# Switcher.net
KiCad netlist of a schematic drawn in Altium Designer
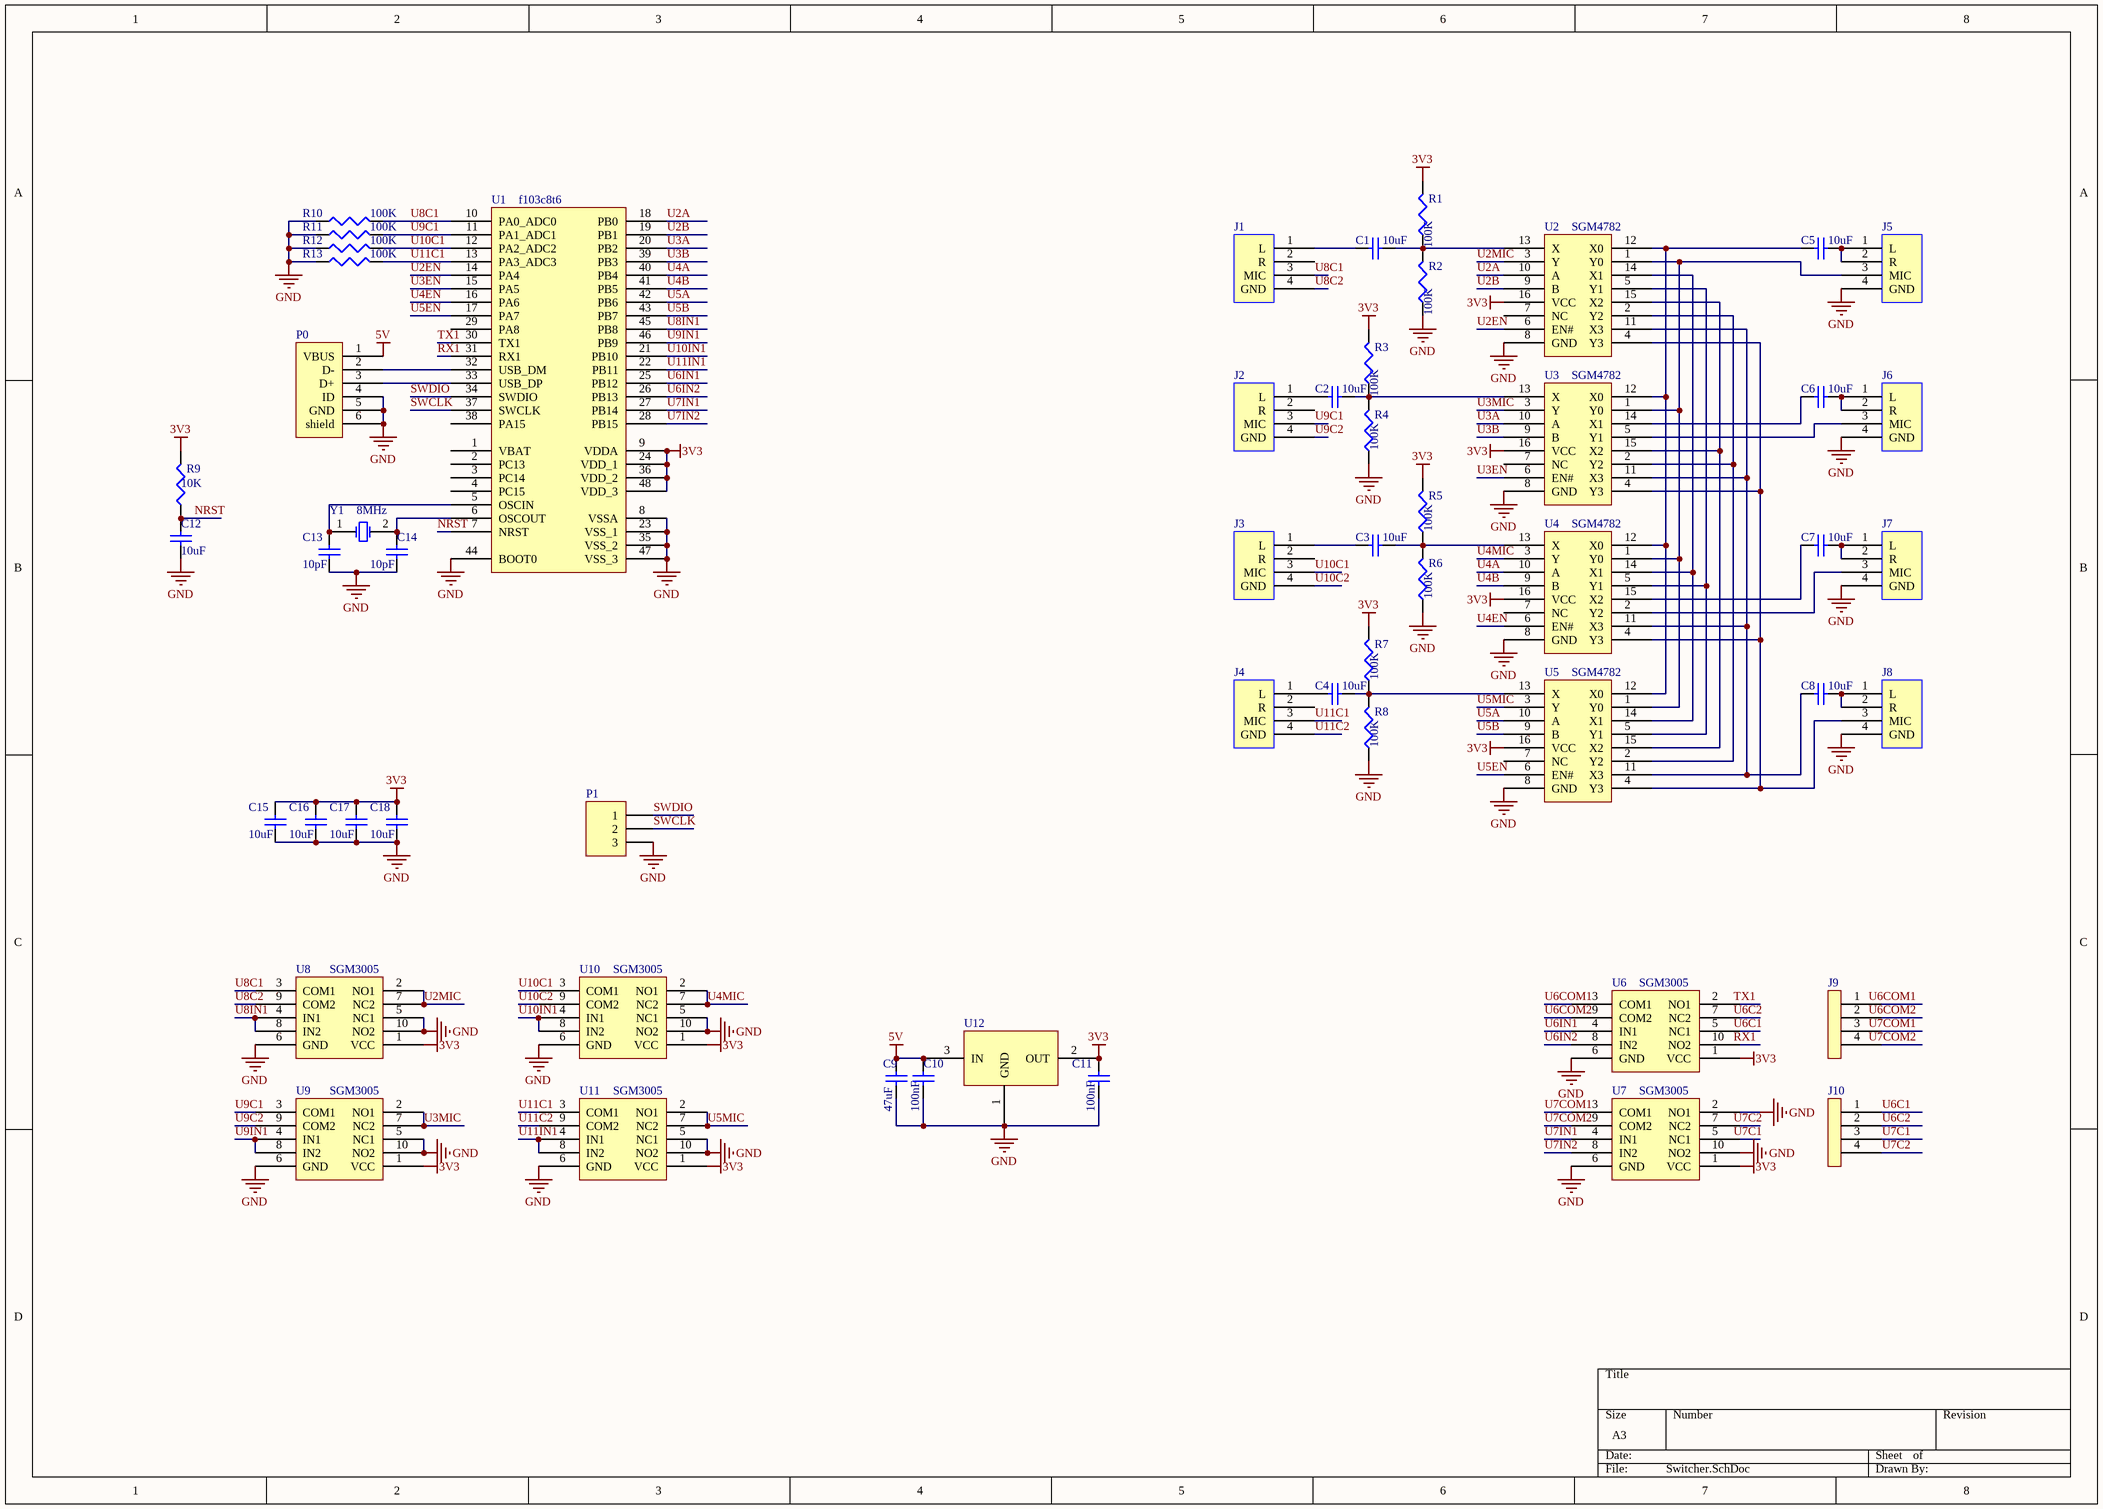
[diagram p0: Switcher.SchDoc]

(export (version "E")
  (design (tool "Eeschema 10.0.6"))
  (components
    (comp (ref "C1")
      (value "10uF")
      (footprint "1608(0603C)")
      (description "Capacitor")
      (fields (field (name "PUBLISHER") "Altium Limited"))
      (libsource (lib "Miscellaneous Devices") (part "Cap"))
    )
    (comp (ref "C2")
      (value "10uF")
      (footprint "1608(0603C)")
      (description "Capacitor")
      (fields (field (name "PUBLISHER") "Altium Limited"))
      (libsource (lib "Miscellaneous Devices") (part "Cap"))
    )
    (comp (ref "C3")
      (value "10uF")
      (footprint "1608(0603C)")
      (description "Capacitor")
      (fields (field (name "PUBLISHER") "Altium Limited"))
      (libsource (lib "Miscellaneous Devices") (part "Cap"))
    )
    (comp (ref "C4")
      (value "10uF")
      (footprint "1608(0603C)")
      (description "Capacitor")
      (fields (field (name "PUBLISHER") "Altium Limited"))
      (libsource (lib "Miscellaneous Devices") (part "Cap"))
    )
    (comp (ref "C5")
      (value "10uF")
      (footprint "1608(0603C)")
      (description "Capacitor")
      (fields (field (name "PUBLISHER") "Altium Limited"))
      (libsource (lib "Miscellaneous Devices") (part "Cap"))
    )
    (comp (ref "C6")
      (value "10uF")
      (footprint "1608(0603C)")
      (description "Capacitor")
      (fields (field (name "PUBLISHER") "Altium Limited"))
      (libsource (lib "Miscellaneous Devices") (part "Cap"))
    )
    (comp (ref "C7")
      (value "10uF")
      (footprint "1608(0603C)")
      (description "Capacitor")
      (fields (field (name "PUBLISHER") "Altium Limited"))
      (libsource (lib "Miscellaneous Devices") (part "Cap"))
    )
    (comp (ref "C8")
      (value "10uF")
      (footprint "1608(0603C)")
      (description "Capacitor")
      (fields (field (name "PUBLISHER") "Altium Limited"))
      (libsource (lib "Miscellaneous Devices") (part "Cap"))
    )
    (comp (ref "C9")
      (value "47uF")
      (footprint "1608(0603C)")
      (description "Capacitor")
      (fields (field (name "PUBLISHER") "Altium Limited"))
      (libsource (lib "Miscellaneous Devices") (part "Cap"))
    )
    (comp (ref "C10")
      (value "100nF")
      (footprint "1608(0603C)")
      (description "Capacitor")
      (fields (field (name "PUBLISHER") "Altium Limited"))
      (libsource (lib "Miscellaneous Devices") (part "Cap"))
    )
    (comp (ref "C11")
      (value "100nF")
      (footprint "1608(0603C)")
      (description "Capacitor")
      (fields (field (name "PUBLISHER") "Altium Limited"))
      (libsource (lib "Miscellaneous Devices") (part "Cap"))
    )
    (comp (ref "C12")
      (value "10uF")
      (footprint "1608(0603C)")
      (description "Capacitor")
      (fields (field (name "PUBLISHER") "Altium Limited"))
      (libsource (lib "Miscellaneous Devices") (part "Cap"))
    )
    (comp (ref "C13")
      (value "10pF")
      (footprint "1608(0603C)")
      (description "Capacitor")
      (fields (field (name "PUBLISHER") "Altium Limited"))
      (libsource (lib "Miscellaneous Devices") (part "Cap"))
    )
    (comp (ref "C14")
      (value "10pF")
      (footprint "1608(0603C)")
      (description "Capacitor")
      (fields (field (name "PUBLISHER") "Altium Limited"))
      (libsource (lib "Miscellaneous Devices") (part "Cap"))
    )
    (comp (ref "C15")
      (value "10uF")
      (footprint "1608(0603C)")
      (description "Capacitor")
      (fields (field (name "PUBLISHER") "Altium Limited"))
      (libsource (lib "Miscellaneous Devices") (part "Cap"))
    )
    (comp (ref "C16")
      (value "10uF")
      (footprint "1608(0603C)")
      (description "Capacitor")
      (fields (field (name "PUBLISHER") "Altium Limited"))
      (libsource (lib "Miscellaneous Devices") (part "Cap"))
    )
    (comp (ref "C17")
      (value "10uF")
      (footprint "1608(0603C)")
      (description "Capacitor")
      (fields (field (name "PUBLISHER") "Altium Limited"))
      (libsource (lib "Miscellaneous Devices") (part "Cap"))
    )
    (comp (ref "C18")
      (value "10uF")
      (footprint "1608(0603C)")
      (description "Capacitor")
      (fields (field (name "PUBLISHER") "Altium Limited"))
      (libsource (lib "Miscellaneous Devices") (part "Cap"))
    )
    (comp (ref "J1") (value "~") (footprint "PJ-322") (libsource (lib "Switcher") (part "seg-4")))
    (comp (ref "J2") (value "~") (footprint "PJ-322") (libsource (lib "Switcher") (part "seg-4")))
    (comp (ref "J3") (value "~") (footprint "PJ-322") (libsource (lib "Switcher") (part "seg-4")))
    (comp (ref "J4") (value "~") (footprint "PJ-322") (libsource (lib "Switcher") (part "seg-4")))
    (comp (ref "J5")
      (value "~")
      (footprint "PJ-322")
      (description "OMTP")
      (libsource (lib "") (part "seg-4_1"))
    )
    (comp (ref "J6") (value "~") (footprint "PJ-322") (libsource (lib "") (part "seg-4_1")))
    (comp (ref "J7") (value "~") (footprint "PJ-322") (libsource (lib "") (part "seg-4_1")))
    (comp (ref "J8") (value "~") (footprint "PJ-322") (libsource (lib "") (part "seg-4_1")))
    (comp (ref "J9") (value "~") (footprint "PJ-322") (libsource (lib "Switcher") (part "CON4")))
    (comp (ref "J10") (value "~") (footprint "PJ-322") (libsource (lib "Switcher") (part "CON4")))
    (comp (ref "P0") (value "~") (footprint "USB_MICRO") (libsource (lib "Switcher") (part "micro_usb")))
    (comp (ref "P1")
      (value "~")
      (footprint "SIP3")
      (description "Header, 3-Pin")
      (fields (field (name "PUBLISHER") "Altium Limited"))
      (libsource (lib "Miscellaneous Connectors") (part "Header 3"))
    )
    (comp (ref "R1")
      (value "100K")
      (footprint "1608(0603R)")
      (description "Resistor")
      (fields (field (name "PUBLISHER") "Altium Limited"))
      (libsource (lib "Miscellaneous Devices") (part "Res3"))
    )
    (comp (ref "R2")
      (value "100K")
      (footprint "1608(0603R)")
      (description "Resistor")
      (fields (field (name "PUBLISHER") "Altium Limited"))
      (libsource (lib "Miscellaneous Devices") (part "Res3"))
    )
    (comp (ref "R3")
      (value "100K")
      (footprint "1608(0603R)")
      (description "Resistor")
      (fields (field (name "PUBLISHER") "Altium Limited"))
      (libsource (lib "Miscellaneous Devices") (part "Res3"))
    )
    (comp (ref "R4")
      (value "100K")
      (footprint "1608(0603R)")
      (description "Resistor")
      (fields (field (name "PUBLISHER") "Altium Limited"))
      (libsource (lib "Miscellaneous Devices") (part "Res3"))
    )
    (comp (ref "R5")
      (value "100K")
      (footprint "1608(0603R)")
      (description "Resistor")
      (fields (field (name "PUBLISHER") "Altium Limited"))
      (libsource (lib "Miscellaneous Devices") (part "Res3"))
    )
    (comp (ref "R6")
      (value "100K")
      (footprint "1608(0603R)")
      (description "Resistor")
      (fields (field (name "PUBLISHER") "Altium Limited"))
      (libsource (lib "Miscellaneous Devices") (part "Res3"))
    )
    (comp (ref "R7")
      (value "100K")
      (footprint "1608(0603R)")
      (description "Resistor")
      (fields (field (name "PUBLISHER") "Altium Limited"))
      (libsource (lib "Miscellaneous Devices") (part "Res3"))
    )
    (comp (ref "R8")
      (value "100K")
      (footprint "1608(0603R)")
      (description "Resistor")
      (fields (field (name "PUBLISHER") "Altium Limited"))
      (libsource (lib "Miscellaneous Devices") (part "Res3"))
    )
    (comp (ref "R9")
      (value "10K")
      (footprint "1608(0603R)")
      (description "Resistor")
      (fields (field (name "PUBLISHER") "Altium Limited"))
      (libsource (lib "Miscellaneous Devices") (part "Res3"))
    )
    (comp (ref "R10")
      (value "100K")
      (footprint "1608(0603R)")
      (description "Resistor")
      (fields (field (name "PUBLISHER") "Altium Limited"))
      (libsource (lib "Miscellaneous Devices") (part "Res3"))
    )
    (comp (ref "R11")
      (value "100K")
      (footprint "1608(0603R)")
      (description "Resistor")
      (fields (field (name "PUBLISHER") "Altium Limited"))
      (libsource (lib "Miscellaneous Devices") (part "Res3"))
    )
    (comp (ref "R12")
      (value "100K")
      (footprint "1608(0603R)")
      (description "Resistor")
      (fields (field (name "PUBLISHER") "Altium Limited"))
      (libsource (lib "Miscellaneous Devices") (part "Res3"))
    )
    (comp (ref "R13")
      (value "100K")
      (footprint "1608(0603R)")
      (description "Resistor")
      (fields (field (name "PUBLISHER") "Altium Limited"))
      (libsource (lib "Miscellaneous Devices") (part "Res3"))
    )
    (comp (ref "U1") (value "f103c8t6") (footprint "LQFP48") (libsource (lib "Switcher") (part "f103c8t6")))
    (comp (ref "U2") (value "SGM4782") (footprint "TSSOP-16") (libsource (lib "Switcher") (part "SGM4782")))
    (comp (ref "U3") (value "SGM4782") (footprint "TSSOP-16") (libsource (lib "Switcher") (part "SGM4782")))
    (comp (ref "U4") (value "SGM4782") (footprint "TSSOP-16") (libsource (lib "Switcher") (part "SGM4782")))
    (comp (ref "U5") (value "SGM4782") (footprint "TSSOP-16") (libsource (lib "Switcher") (part "SGM4782")))
    (comp (ref "U6") (value "SGM3005") (footprint "MSOP-10") (libsource (lib "Switcher") (part "SGM3005")))
    (comp (ref "U7") (value "SGM3005") (footprint "MSOP-10") (libsource (lib "Switcher") (part "SGM3005")))
    (comp (ref "U8") (value "SGM3005") (footprint "MSOP-10") (libsource (lib "Switcher") (part "SGM3005")))
    (comp (ref "U9") (value "SGM3005") (footprint "MSOP-10") (libsource (lib "Switcher") (part "SGM3005")))
    (comp (ref "U10") (value "SGM3005") (footprint "MSOP-10") (libsource (lib "Switcher") (part "SGM3005")))
    (comp (ref "U11") (value "SGM3005") (footprint "MSOP-10") (libsource (lib "Switcher") (part "SGM3005")))
    (comp (ref "U12") (value "~") (footprint "SOT-223") (libsource (lib "Switcher") (part "ASM1117-3.3")))
    (comp (ref "Y1")
      (value "8MHz")
      (footprint "XTAL1")
      (description "Crystal Oscillator")
      (fields (field (name "PUBLISHER") "Altium Limited"))
      (libsource (lib "Miscellaneous Devices") (part "XTAL"))
    )
  )
  (nets
    (net (code "1") (name "/NRST") (class "Default")
      (node (ref "C12") (pin "2") (pinfunction "2_2") (pintype "passive"))
      (node (ref "R9") (pin "1") (pinfunction "1_1") (pintype "passive"))
      (node (ref "U1") (pin "7") (pinfunction "NRST_7") (pintype "passive"))
    )
    (net (code "2") (name "/RX1") (class "Default")
      (node (ref "U1") (pin "31") (pinfunction "RX1_31") (pintype "passive"))
    )
    (net (code "3") (name "/SWCLK") (class "Default")
      (node (ref "P1") (pin "2") (pinfunction "2_2") (pintype "passive"))
      (node (ref "U1") (pin "37") (pinfunction "SWCLK_37") (pintype "passive"))
    )
    (net (code "4") (name "/SWDIO") (class "Default")
      (node (ref "P1") (pin "1") (pinfunction "1_1") (pintype "passive"))
      (node (ref "U1") (pin "34") (pinfunction "SWDIO_34") (pintype "passive"))
    )
    (net (code "5") (name "/TX1") (class "Default")
      (node (ref "U1") (pin "30") (pinfunction "TX1_30") (pintype "passive"))
    )
    (net (code "6") (name "/U2A") (class "Default")
      (node (ref "U1") (pin "18") (pinfunction "PB0_18") (pintype "passive"))
      (node (ref "U2") (pin "10") (pinfunction "A_10") (pintype "passive"))
    )
    (net (code "7") (name "/U2B") (class "Default")
      (node (ref "U1") (pin "19") (pinfunction "PB1_19") (pintype "passive"))
      (node (ref "U2") (pin "9") (pinfunction "B_9") (pintype "passive"))
    )
    (net (code "8") (name "/U2EN") (class "Default")
      (node (ref "U1") (pin "14") (pinfunction "PA4_14") (pintype "passive"))
      (node (ref "U2") (pin "6") (pinfunction "EN#_6") (pintype "passive"))
    )
    (net (code "9") (name "/U2MIC") (class "Default")
      (node (ref "U2") (pin "3") (pinfunction "Y_3") (pintype "passive"))
      (node (ref "U8") (pin "2") (pinfunction "NO1_2") (pintype "passive"))
      (node (ref "U8") (pin "7") (pinfunction "NC2_7") (pintype "passive"))
    )
    (net (code "10") (name "/U3A") (class "Default")
      (node (ref "U1") (pin "20") (pinfunction "PB2_20") (pintype "passive"))
      (node (ref "U3") (pin "10") (pinfunction "A_10") (pintype "passive"))
    )
    (net (code "11") (name "/U3B") (class "Default")
      (node (ref "U1") (pin "39") (pinfunction "PB3_39") (pintype "passive"))
      (node (ref "U3") (pin "9") (pinfunction "B_9") (pintype "passive"))
    )
    (net (code "12") (name "/U3EN") (class "Default")
      (node (ref "U1") (pin "15") (pinfunction "PA5_15") (pintype "passive"))
      (node (ref "U3") (pin "6") (pinfunction "EN#_6") (pintype "passive"))
    )
    (net (code "13") (name "/U3MIC") (class "Default")
      (node (ref "U3") (pin "3") (pinfunction "Y_3") (pintype "passive"))
      (node (ref "U9") (pin "2") (pinfunction "NO1_2") (pintype "passive"))
      (node (ref "U9") (pin "7") (pinfunction "NC2_7") (pintype "passive"))
    )
    (net (code "14") (name "/U4A") (class "Default")
      (node (ref "U1") (pin "40") (pinfunction "PB4_40") (pintype "passive"))
      (node (ref "U4") (pin "10") (pinfunction "A_10") (pintype "passive"))
    )
    (net (code "15") (name "/U4B") (class "Default")
      (node (ref "U1") (pin "41") (pinfunction "PB5_41") (pintype "passive"))
      (node (ref "U4") (pin "9") (pinfunction "B_9") (pintype "passive"))
    )
    (net (code "16") (name "/U4EN") (class "Default")
      (node (ref "U1") (pin "16") (pinfunction "PA6_16") (pintype "passive"))
      (node (ref "U4") (pin "6") (pinfunction "EN#_6") (pintype "passive"))
    )
    (net (code "17") (name "/U4MIC") (class "Default")
      (node (ref "U10") (pin "2") (pinfunction "NO1_2") (pintype "passive"))
      (node (ref "U10") (pin "7") (pinfunction "NC2_7") (pintype "passive"))
      (node (ref "U4") (pin "3") (pinfunction "Y_3") (pintype "passive"))
    )
    (net (code "18") (name "/U5A") (class "Default")
      (node (ref "U1") (pin "42") (pinfunction "PB6_42") (pintype "passive"))
      (node (ref "U5") (pin "10") (pinfunction "A_10") (pintype "passive"))
    )
    (net (code "19") (name "/U5B") (class "Default")
      (node (ref "U1") (pin "43") (pinfunction "PB7_43") (pintype "passive"))
      (node (ref "U5") (pin "9") (pinfunction "B_9") (pintype "passive"))
    )
    (net (code "20") (name "/U5EN") (class "Default")
      (node (ref "U1") (pin "17") (pinfunction "PA7_17") (pintype "passive"))
      (node (ref "U5") (pin "6") (pinfunction "EN#_6") (pintype "passive"))
    )
    (net (code "21") (name "/U5MIC") (class "Default")
      (node (ref "U11") (pin "2") (pinfunction "NO1_2") (pintype "passive"))
      (node (ref "U11") (pin "7") (pinfunction "NC2_7") (pintype "passive"))
      (node (ref "U5") (pin "3") (pinfunction "Y_3") (pintype "passive"))
    )
    (net (code "22") (name "/U6C1") (class "Default") (node (ref "J10") (pin "1") (pintype "passive")))
    (net (code "23") (name "/U6C2") (class "Default") (node (ref "J10") (pin "2") (pintype "passive")))
    (net (code "24") (name "/U6COM1") (class "Default")
      (node (ref "U6") (pin "3") (pinfunction "COM1_3") (pintype "passive"))
    )
    (net (code "25") (name "/U6COM2") (class "Default")
      (node (ref "U6") (pin "9") (pinfunction "COM2_9") (pintype "passive"))
    )
    (net (code "26") (name "/U6IN1") (class "Default")
      (node (ref "U1") (pin "25") (pinfunction "PB12_25") (pintype "passive"))
      (node (ref "U6") (pin "4") (pinfunction "IN1_4") (pintype "passive"))
    )
    (net (code "27") (name "/U6IN2") (class "Default")
      (node (ref "U1") (pin "26") (pinfunction "PB13_26") (pintype "passive"))
      (node (ref "U6") (pin "8") (pinfunction "IN2_8") (pintype "passive"))
    )
    (net (code "28") (name "/U7C1") (class "Default") (node (ref "J10") (pin "3") (pintype "passive")))
    (net (code "29") (name "/U7C2") (class "Default") (node (ref "J10") (pin "4") (pintype "passive")))
    (net (code "30") (name "/U7COM1") (class "Default")
      (node (ref "U7") (pin "3") (pinfunction "COM1_3") (pintype "passive"))
    )
    (net (code "31") (name "/U7COM2") (class "Default")
      (node (ref "U7") (pin "9") (pinfunction "COM2_9") (pintype "passive"))
    )
    (net (code "32") (name "/U7IN1") (class "Default")
      (node (ref "U1") (pin "27") (pinfunction "PB14_27") (pintype "passive"))
      (node (ref "U7") (pin "4") (pinfunction "IN1_4") (pintype "passive"))
    )
    (net (code "33") (name "/U7IN2") (class "Default")
      (node (ref "U1") (pin "28") (pinfunction "PB15_28") (pintype "passive"))
      (node (ref "U7") (pin "8") (pinfunction "IN2_8") (pintype "passive"))
    )
    (net (code "34") (name "/U8C1") (class "Default")
      (node (ref "J1") (pin "3") (pinfunction "MIC_3") (pintype "passive"))
      (node (ref "R10") (pin "2") (pinfunction "2_2") (pintype "passive"))
      (node (ref "U1") (pin "10") (pinfunction "PA0_ADC0_10") (pintype "passive"))
      (node (ref "U8") (pin "3") (pinfunction "COM1_3") (pintype "passive"))
    )
    (net (code "35") (name "/U8C2") (class "Default")
      (node (ref "J1") (pin "4") (pinfunction "GND_4") (pintype "passive"))
      (node (ref "U8") (pin "9") (pinfunction "COM2_9") (pintype "passive"))
    )
    (net (code "36") (name "/U8IN1") (class "Default")
      (node (ref "U1") (pin "45") (pinfunction "PB8_45") (pintype "passive"))
      (node (ref "U8") (pin "4") (pinfunction "IN1_4") (pintype "passive"))
      (node (ref "U8") (pin "8") (pinfunction "IN2_8") (pintype "passive"))
    )
    (net (code "37") (name "/U9C1") (class "Default")
      (node (ref "J2") (pin "3") (pinfunction "MIC_3") (pintype "passive"))
      (node (ref "R11") (pin "2") (pinfunction "2_2") (pintype "passive"))
      (node (ref "U1") (pin "11") (pinfunction "PA1_ADC1_11") (pintype "passive"))
      (node (ref "U9") (pin "3") (pinfunction "COM1_3") (pintype "passive"))
    )
    (net (code "38") (name "/U9C2") (class "Default")
      (node (ref "J2") (pin "4") (pinfunction "GND_4") (pintype "passive"))
      (node (ref "U9") (pin "9") (pinfunction "COM2_9") (pintype "passive"))
    )
    (net (code "39") (name "/U9IN1") (class "Default")
      (node (ref "U1") (pin "46") (pinfunction "PB9_46") (pintype "passive"))
      (node (ref "U9") (pin "4") (pinfunction "IN1_4") (pintype "passive"))
      (node (ref "U9") (pin "8") (pinfunction "IN2_8") (pintype "passive"))
    )
    (net (code "40") (name "/U10C1") (class "Default")
      (node (ref "J3") (pin "3") (pinfunction "MIC_3") (pintype "passive"))
      (node (ref "R12") (pin "2") (pinfunction "2_2") (pintype "passive"))
      (node (ref "U1") (pin "12") (pinfunction "PA2_ADC2_12") (pintype "passive"))
      (node (ref "U10") (pin "3") (pinfunction "COM1_3") (pintype "passive"))
    )
    (net (code "41") (name "/U10C2") (class "Default")
      (node (ref "J3") (pin "4") (pinfunction "GND_4") (pintype "passive"))
      (node (ref "U10") (pin "9") (pinfunction "COM2_9") (pintype "passive"))
    )
    (net (code "42") (name "/U10IN1") (class "Default")
      (node (ref "U1") (pin "21") (pinfunction "PB10_21") (pintype "passive"))
      (node (ref "U10") (pin "4") (pinfunction "IN1_4") (pintype "passive"))
      (node (ref "U10") (pin "8") (pinfunction "IN2_8") (pintype "passive"))
    )
    (net (code "43") (name "/U11C1") (class "Default")
      (node (ref "J4") (pin "3") (pinfunction "MIC_3") (pintype "passive"))
      (node (ref "R13") (pin "2") (pinfunction "2_2") (pintype "passive"))
      (node (ref "U1") (pin "13") (pinfunction "PA3_ADC3_13") (pintype "passive"))
      (node (ref "U11") (pin "3") (pinfunction "COM1_3") (pintype "passive"))
    )
    (net (code "44") (name "/U11C2") (class "Default")
      (node (ref "J4") (pin "4") (pinfunction "GND_4") (pintype "passive"))
      (node (ref "U11") (pin "9") (pinfunction "COM2_9") (pintype "passive"))
    )
    (net (code "45") (name "/U11IN1") (class "Default")
      (node (ref "U1") (pin "22") (pinfunction "PB11_22") (pintype "passive"))
      (node (ref "U11") (pin "4") (pinfunction "IN1_4") (pintype "passive"))
      (node (ref "U11") (pin "8") (pinfunction "IN2_8") (pintype "passive"))
    )
    (net (code "46") (name "3V3") (class "Default")
      (node (ref "C11") (pin "2") (pinfunction "2_2") (pintype "passive"))
      (node (ref "C15") (pin "2") (pinfunction "2_2") (pintype "passive"))
      (node (ref "C16") (pin "2") (pinfunction "2_2") (pintype "passive"))
      (node (ref "C17") (pin "2") (pinfunction "2_2") (pintype "passive"))
      (node (ref "C18") (pin "2") (pinfunction "2_2") (pintype "passive"))
      (node (ref "R1") (pin "2") (pinfunction "2_2") (pintype "passive"))
      (node (ref "R3") (pin "2") (pinfunction "2_2") (pintype "passive"))
      (node (ref "R5") (pin "2") (pinfunction "2_2") (pintype "passive"))
      (node (ref "R7") (pin "2") (pinfunction "2_2") (pintype "passive"))
      (node (ref "R9") (pin "2") (pinfunction "2_2") (pintype "passive"))
      (node (ref "U1") (pin "24") (pinfunction "VDD_1_24") (pintype "passive"))
      (node (ref "U1") (pin "36") (pinfunction "VDD_2_36") (pintype "passive"))
      (node (ref "U1") (pin "48") (pinfunction "VDD_3_48") (pintype "passive"))
      (node (ref "U1") (pin "9") (pinfunction "VDDA_9") (pintype "passive"))
      (node (ref "U10") (pin "1") (pinfunction "VCC_1") (pintype "passive"))
      (node (ref "U11") (pin "1") (pinfunction "VCC_1") (pintype "passive"))
      (node (ref "U12") (pin "2") (pinfunction "OUT_2") (pintype "passive"))
      (node (ref "U2") (pin "16") (pinfunction "VCC_16") (pintype "passive"))
      (node (ref "U3") (pin "16") (pinfunction "VCC_16") (pintype "passive"))
      (node (ref "U4") (pin "16") (pinfunction "VCC_16") (pintype "passive"))
      (node (ref "U5") (pin "16") (pinfunction "VCC_16") (pintype "passive"))
      (node (ref "U6") (pin "1") (pinfunction "VCC_1") (pintype "passive"))
      (node (ref "U7") (pin "1") (pinfunction "VCC_1") (pintype "passive"))
      (node (ref "U8") (pin "1") (pinfunction "VCC_1") (pintype "passive"))
      (node (ref "U9") (pin "1") (pinfunction "VCC_1") (pintype "passive"))
    )
    (net (code "47") (name "5V") (class "Default")
      (node (ref "C10") (pin "2") (pinfunction "2_2") (pintype "passive"))
      (node (ref "C9") (pin "2") (pinfunction "2_2") (pintype "passive"))
      (node (ref "P0") (pin "1") (pinfunction "VBUS_1") (pintype "passive"))
      (node (ref "U12") (pin "3") (pinfunction "IN_3") (pintype "passive"))
    )
    (net (code "48") (name "GND") (class "Default")
      (node (ref "C10") (pin "1") (pinfunction "1_1") (pintype "passive"))
      (node (ref "C11") (pin "1") (pinfunction "1_1") (pintype "passive"))
      (node (ref "C12") (pin "1") (pinfunction "1_1") (pintype "passive"))
      (node (ref "C13") (pin "1") (pinfunction "1_1") (pintype "passive"))
      (node (ref "C14") (pin "1") (pinfunction "1_1") (pintype "passive"))
      (node (ref "C15") (pin "1") (pinfunction "1_1") (pintype "passive"))
      (node (ref "C16") (pin "1") (pinfunction "1_1") (pintype "passive"))
      (node (ref "C17") (pin "1") (pinfunction "1_1") (pintype "passive"))
      (node (ref "C18") (pin "1") (pinfunction "1_1") (pintype "passive"))
      (node (ref "C9") (pin "1") (pinfunction "1_1") (pintype "passive"))
      (node (ref "J5") (pin "4") (pinfunction "GND_4") (pintype "passive"))
      (node (ref "J6") (pin "4") (pinfunction "GND_4") (pintype "passive"))
      (node (ref "J7") (pin "4") (pinfunction "GND_4") (pintype "passive"))
      (node (ref "J8") (pin "4") (pinfunction "GND_4") (pintype "passive"))
      (node (ref "P0") (pin "4") (pinfunction "ID_4") (pintype "passive"))
      (node (ref "P0") (pin "5") (pinfunction "GND_5") (pintype "passive"))
      (node (ref "P0") (pin "6") (pinfunction "shield_6") (pintype "passive"))
      (node (ref "P1") (pin "3") (pinfunction "3_3") (pintype "passive"))
      (node (ref "R10") (pin "1") (pinfunction "1_1") (pintype "passive"))
      (node (ref "R11") (pin "1") (pinfunction "1_1") (pintype "passive"))
      (node (ref "R12") (pin "1") (pinfunction "1_1") (pintype "passive"))
      (node (ref "R13") (pin "1") (pinfunction "1_1") (pintype "passive"))
      (node (ref "R2") (pin "1") (pinfunction "1_1") (pintype "passive"))
      (node (ref "R4") (pin "1") (pinfunction "1_1") (pintype "passive"))
      (node (ref "R6") (pin "1") (pinfunction "1_1") (pintype "passive"))
      (node (ref "R8") (pin "1") (pinfunction "1_1") (pintype "passive"))
      (node (ref "U1") (pin "23") (pinfunction "VSS_1_23") (pintype "passive"))
      (node (ref "U1") (pin "35") (pinfunction "VSS_2_35") (pintype "passive"))
      (node (ref "U1") (pin "44") (pinfunction "BOOT0_44") (pintype "passive"))
      (node (ref "U1") (pin "47") (pinfunction "VSS_3_47") (pintype "passive"))
      (node (ref "U1") (pin "8") (pinfunction "VSSA_8") (pintype "passive"))
      (node (ref "U10") (pin "10") (pinfunction "NO2_10") (pintype "passive"))
      (node (ref "U10") (pin "5") (pinfunction "NC1_5") (pintype "passive"))
      (node (ref "U10") (pin "6") (pinfunction "GND_6") (pintype "passive"))
      (node (ref "U11") (pin "10") (pinfunction "NO2_10") (pintype "passive"))
      (node (ref "U11") (pin "5") (pinfunction "NC1_5") (pintype "passive"))
      (node (ref "U11") (pin "6") (pinfunction "GND_6") (pintype "passive"))
      (node (ref "U12") (pin "1") (pinfunction "GND_1") (pintype "passive"))
      (node (ref "U2") (pin "8") (pinfunction "GND_8") (pintype "passive"))
      (node (ref "U3") (pin "8") (pinfunction "GND_8") (pintype "passive"))
      (node (ref "U4") (pin "8") (pinfunction "GND_8") (pintype "passive"))
      (node (ref "U5") (pin "8") (pinfunction "GND_8") (pintype "passive"))
      (node (ref "U6") (pin "6") (pinfunction "GND_6") (pintype "passive"))
      (node (ref "U7") (pin "10") (pinfunction "NO2_10") (pintype "passive"))
      (node (ref "U7") (pin "2") (pinfunction "NO1_2") (pintype "passive"))
      (node (ref "U7") (pin "6") (pinfunction "GND_6") (pintype "passive"))
      (node (ref "U8") (pin "10") (pinfunction "NO2_10") (pintype "passive"))
      (node (ref "U8") (pin "5") (pinfunction "NC1_5") (pintype "passive"))
      (node (ref "U8") (pin "6") (pinfunction "GND_6") (pintype "passive"))
      (node (ref "U9") (pin "10") (pinfunction "NO2_10") (pintype "passive"))
      (node (ref "U9") (pin "5") (pinfunction "NC1_5") (pintype "passive"))
      (node (ref "U9") (pin "6") (pinfunction "GND_6") (pintype "passive"))
    )
    (net (code "49") (name "Net-(J1-L)") (class "Default")
      (node (ref "C1") (pin "1") (pinfunction "1_1") (pintype "passive"))
      (node (ref "J1") (pin "1") (pinfunction "L_1") (pintype "passive"))
    )
    (net (code "50") (name "Net-(J2-L)") (class "Default")
      (node (ref "C2") (pin "1") (pinfunction "1_1") (pintype "passive"))
      (node (ref "J2") (pin "1") (pinfunction "L_1") (pintype "passive"))
    )
    (net (code "51") (name "Net-(J3-L)") (class "Default")
      (node (ref "C3") (pin "1") (pinfunction "1_1") (pintype "passive"))
      (node (ref "J3") (pin "1") (pinfunction "L_1") (pintype "passive"))
    )
    (net (code "52") (name "Net-(J4-L)") (class "Default")
      (node (ref "C4") (pin "1") (pinfunction "1_1") (pintype "passive"))
      (node (ref "J4") (pin "1") (pinfunction "L_1") (pintype "passive"))
    )
    (net (code "53") (name "Net-(J5-L)") (class "Default")
      (node (ref "C5") (pin "2") (pinfunction "2_2") (pintype "passive"))
      (node (ref "J5") (pin "1") (pinfunction "L_1") (pintype "passive"))
      (node (ref "J5") (pin "2") (pinfunction "R_2") (pintype "passive"))
    )
    (net (code "54") (name "Net-(J5-MIC)") (class "Default")
      (node (ref "J5") (pin "3") (pinfunction "MIC_3") (pintype "passive"))
      (node (ref "U2") (pin "1") (pinfunction "Y0_1") (pintype "passive"))
      (node (ref "U3") (pin "1") (pinfunction "Y0_1") (pintype "passive"))
      (node (ref "U4") (pin "1") (pinfunction "Y0_1") (pintype "passive"))
      (node (ref "U5") (pin "1") (pinfunction "Y0_1") (pintype "passive"))
    )
    (net (code "55") (name "Net-(J6-L)") (class "Default")
      (node (ref "C6") (pin "2") (pinfunction "2_2") (pintype "passive"))
      (node (ref "J6") (pin "1") (pinfunction "L_1") (pintype "passive"))
      (node (ref "J6") (pin "2") (pinfunction "R_2") (pintype "passive"))
    )
    (net (code "56") (name "Net-(J6-MIC)") (class "Default")
      (node (ref "J6") (pin "3") (pinfunction "MIC_3") (pintype "passive"))
      (node (ref "U3") (pin "5") (pinfunction "Y1_5") (pintype "passive"))
    )
    (net (code "57") (name "Net-(J7-L)") (class "Default")
      (node (ref "C7") (pin "2") (pinfunction "2_2") (pintype "passive"))
      (node (ref "J7") (pin "1") (pinfunction "L_1") (pintype "passive"))
      (node (ref "J7") (pin "2") (pinfunction "R_2") (pintype "passive"))
    )
    (net (code "58") (name "Net-(J7-MIC)") (class "Default")
      (node (ref "J7") (pin "3") (pinfunction "MIC_3") (pintype "passive"))
      (node (ref "U4") (pin "2") (pinfunction "Y2_2") (pintype "passive"))
    )
    (net (code "59") (name "Net-(J8-L)") (class "Default")
      (node (ref "C8") (pin "2") (pinfunction "2_2") (pintype "passive"))
      (node (ref "J8") (pin "1") (pinfunction "L_1") (pintype "passive"))
      (node (ref "J8") (pin "2") (pinfunction "R_2") (pintype "passive"))
    )
    (net (code "60") (name "Net-(J8-MIC)") (class "Default")
      (node (ref "J8") (pin "3") (pinfunction "MIC_3") (pintype "passive"))
      (node (ref "U2") (pin "4") (pinfunction "Y3_4") (pintype "passive"))
      (node (ref "U3") (pin "4") (pinfunction "Y3_4") (pintype "passive"))
      (node (ref "U4") (pin "4") (pinfunction "Y3_4") (pintype "passive"))
      (node (ref "U5") (pin "4") (pinfunction "Y3_4") (pintype "passive"))
    )
    (net (code "61") (name "Net-(P0-D+)") (class "Default")
      (node (ref "P0") (pin "3") (pinfunction "D+_3") (pintype "passive"))
      (node (ref "U1") (pin "33") (pinfunction "USB_DP_33") (pintype "passive"))
    )
    (net (code "62") (name "Net-(P0-D-)") (class "Default")
      (node (ref "P0") (pin "2") (pinfunction "D-_2") (pintype "passive"))
      (node (ref "U1") (pin "32") (pinfunction "USB_DM_32") (pintype "passive"))
    )
    (net (code "63") (name "Net-(U1-OSCIN)") (class "Default")
      (node (ref "C13") (pin "2") (pinfunction "2_2") (pintype "passive"))
      (node (ref "U1") (pin "5") (pinfunction "OSCIN_5") (pintype "passive"))
      (node (ref "Y1") (pin "1") (pinfunction "OSC1_1") (pintype "passive"))
    )
    (net (code "64") (name "Net-(U1-OSCOUT)") (class "Default")
      (node (ref "C14") (pin "2") (pinfunction "2_2") (pintype "passive"))
      (node (ref "U1") (pin "6") (pinfunction "OSCOUT_6") (pintype "passive"))
      (node (ref "Y1") (pin "2") (pinfunction "OSC2_2") (pintype "passive"))
    )
    (net (code "65") (name "Net-(U2-X)") (class "Default")
      (node (ref "C1") (pin "2") (pinfunction "2_2") (pintype "passive"))
      (node (ref "R1") (pin "1") (pinfunction "1_1") (pintype "passive"))
      (node (ref "R2") (pin "2") (pinfunction "2_2") (pintype "passive"))
      (node (ref "U2") (pin "13") (pinfunction "X_13") (pintype "passive"))
    )
    (net (code "66") (name "Net-(U2-X0)") (class "Default")
      (node (ref "C5") (pin "1") (pinfunction "1_1") (pintype "passive"))
      (node (ref "U2") (pin "12") (pinfunction "X0_12") (pintype "passive"))
      (node (ref "U3") (pin "12") (pinfunction "X0_12") (pintype "passive"))
      (node (ref "U4") (pin "12") (pinfunction "X0_12") (pintype "passive"))
      (node (ref "U5") (pin "12") (pinfunction "X0_12") (pintype "passive"))
    )
    (net (code "67") (name "Net-(U2-X1)") (class "Default")
      (node (ref "U2") (pin "14") (pinfunction "X1_14") (pintype "passive"))
      (node (ref "U4") (pin "14") (pinfunction "X1_14") (pintype "passive"))
      (node (ref "U5") (pin "14") (pinfunction "X1_14") (pintype "passive"))
    )
    (net (code "68") (name "Net-(U2-X2)") (class "Default")
      (node (ref "U2") (pin "15") (pinfunction "X2_15") (pintype "passive"))
      (node (ref "U3") (pin "15") (pinfunction "X2_15") (pintype "passive"))
      (node (ref "U5") (pin "15") (pinfunction "X2_15") (pintype "passive"))
    )
    (net (code "69") (name "Net-(U2-X3)") (class "Default")
      (node (ref "C8") (pin "1") (pinfunction "1_1") (pintype "passive"))
      (node (ref "U2") (pin "11") (pinfunction "X3_11") (pintype "passive"))
      (node (ref "U3") (pin "11") (pinfunction "X3_11") (pintype "passive"))
      (node (ref "U4") (pin "11") (pinfunction "X3_11") (pintype "passive"))
      (node (ref "U5") (pin "11") (pinfunction "X3_11") (pintype "passive"))
    )
    (net (code "70") (name "Net-(U2-Y1)") (class "Default")
      (node (ref "U2") (pin "5") (pinfunction "Y1_5") (pintype "passive"))
      (node (ref "U4") (pin "5") (pinfunction "Y1_5") (pintype "passive"))
      (node (ref "U5") (pin "5") (pinfunction "Y1_5") (pintype "passive"))
    )
    (net (code "71") (name "Net-(U2-Y2)") (class "Default")
      (node (ref "U2") (pin "2") (pinfunction "Y2_2") (pintype "passive"))
      (node (ref "U3") (pin "2") (pinfunction "Y2_2") (pintype "passive"))
      (node (ref "U5") (pin "2") (pinfunction "Y2_2") (pintype "passive"))
    )
    (net (code "72") (name "Net-(U3-X)") (class "Default")
      (node (ref "C2") (pin "2") (pinfunction "2_2") (pintype "passive"))
      (node (ref "R3") (pin "1") (pinfunction "1_1") (pintype "passive"))
      (node (ref "R4") (pin "2") (pinfunction "2_2") (pintype "passive"))
      (node (ref "U3") (pin "13") (pinfunction "X_13") (pintype "passive"))
    )
    (net (code "73") (name "Net-(U3-X1)") (class "Default")
      (node (ref "C6") (pin "1") (pinfunction "1_1") (pintype "passive"))
      (node (ref "U3") (pin "14") (pinfunction "X1_14") (pintype "passive"))
    )
    (net (code "74") (name "Net-(U4-X)") (class "Default")
      (node (ref "C3") (pin "2") (pinfunction "2_2") (pintype "passive"))
      (node (ref "R5") (pin "1") (pinfunction "1_1") (pintype "passive"))
      (node (ref "R6") (pin "2") (pinfunction "2_2") (pintype "passive"))
      (node (ref "U4") (pin "13") (pinfunction "X_13") (pintype "passive"))
    )
    (net (code "75") (name "Net-(U4-X2)") (class "Default")
      (node (ref "C7") (pin "1") (pinfunction "1_1") (pintype "passive"))
      (node (ref "U4") (pin "15") (pinfunction "X2_15") (pintype "passive"))
    )
    (net (code "76") (name "Net-(U5-X)") (class "Default")
      (node (ref "C4") (pin "2") (pinfunction "2_2") (pintype "passive"))
      (node (ref "R7") (pin "1") (pinfunction "1_1") (pintype "passive"))
      (node (ref "R8") (pin "2") (pinfunction "2_2") (pintype "passive"))
      (node (ref "U5") (pin "13") (pinfunction "X_13") (pintype "passive"))
    )
    (net (code "77") (name "unconnected-(J1-R-Pad2)") (class "Default")
      (node (ref "J1") (pin "2") (pinfunction "R_2") (pintype "passive"))
    )
    (net (code "78") (name "unconnected-(J2-R-Pad2)") (class "Default")
      (node (ref "J2") (pin "2") (pinfunction "R_2") (pintype "passive"))
    )
    (net (code "79") (name "unconnected-(J3-R-Pad2)") (class "Default")
      (node (ref "J3") (pin "2") (pinfunction "R_2") (pintype "passive"))
    )
    (net (code "80") (name "unconnected-(J4-R-Pad2)") (class "Default")
      (node (ref "J4") (pin "2") (pinfunction "R_2") (pintype "passive"))
    )
    (net (code "81") (name "unconnected-(J9-Pad1)") (class "Default")
      (node (ref "J9") (pin "1") (pintype "passive"))
    )
    (net (code "82") (name "unconnected-(J9-Pad2)") (class "Default")
      (node (ref "J9") (pin "2") (pintype "passive"))
    )
    (net (code "83") (name "unconnected-(J9-Pad3)") (class "Default")
      (node (ref "J9") (pin "3") (pintype "passive"))
    )
    (net (code "84") (name "unconnected-(J9-Pad4)") (class "Default")
      (node (ref "J9") (pin "4") (pintype "passive"))
    )
    (net (code "85") (name "unconnected-(U1-PA8-Pad29)") (class "Default")
      (node (ref "U1") (pin "29") (pinfunction "PA8_29") (pintype "passive"))
    )
    (net (code "86") (name "unconnected-(U1-PA15-Pad38)") (class "Default")
      (node (ref "U1") (pin "38") (pinfunction "PA15_38") (pintype "passive"))
    )
    (net (code "87") (name "unconnected-(U1-PC13-Pad2)") (class "Default")
      (node (ref "U1") (pin "2") (pinfunction "PC13_2") (pintype "passive"))
    )
    (net (code "88") (name "unconnected-(U1-PC14-Pad3)") (class "Default")
      (node (ref "U1") (pin "3") (pinfunction "PC14_3") (pintype "passive"))
    )
    (net (code "89") (name "unconnected-(U1-PC15-Pad4)") (class "Default")
      (node (ref "U1") (pin "4") (pinfunction "PC15_4") (pintype "passive"))
    )
    (net (code "90") (name "unconnected-(U1-VBAT-Pad1)") (class "Default")
      (node (ref "U1") (pin "1") (pinfunction "VBAT_1") (pintype "passive"))
    )
    (net (code "91") (name "unconnected-(U2-NC-Pad7)") (class "Default")
      (node (ref "U2") (pin "7") (pinfunction "NC_7") (pintype "passive"))
    )
    (net (code "92") (name "unconnected-(U3-NC-Pad7)") (class "Default")
      (node (ref "U3") (pin "7") (pinfunction "NC_7") (pintype "passive"))
    )
    (net (code "93") (name "unconnected-(U4-NC-Pad7)") (class "Default")
      (node (ref "U4") (pin "7") (pinfunction "NC_7") (pintype "passive"))
    )
    (net (code "94") (name "unconnected-(U5-NC-Pad7)") (class "Default")
      (node (ref "U5") (pin "7") (pinfunction "NC_7") (pintype "passive"))
    )
    (net (code "95") (name "unconnected-(U6-NC1-Pad5)") (class "Default")
      (node (ref "U6") (pin "5") (pinfunction "NC1_5") (pintype "passive"))
    )
    (net (code "96") (name "unconnected-(U6-NC2-Pad7)") (class "Default")
      (node (ref "U6") (pin "7") (pinfunction "NC2_7") (pintype "passive"))
    )
    (net (code "97") (name "unconnected-(U6-NO1-Pad2)") (class "Default")
      (node (ref "U6") (pin "2") (pinfunction "NO1_2") (pintype "passive"))
    )
    (net (code "98") (name "unconnected-(U6-NO2-Pad10)") (class "Default")
      (node (ref "U6") (pin "10") (pinfunction "NO2_10") (pintype "passive"))
    )
    (net (code "99") (name "unconnected-(U7-NC1-Pad5)") (class "Default")
      (node (ref "U7") (pin "5") (pinfunction "NC1_5") (pintype "passive"))
    )
    (net (code "100") (name "unconnected-(U7-NC2-Pad7)") (class "Default")
      (node (ref "U7") (pin "7") (pinfunction "NC2_7") (pintype "passive"))
    )
  )
)
